# RECEIVER.net
KiCad netlist of a schematic drawn in EAGLE
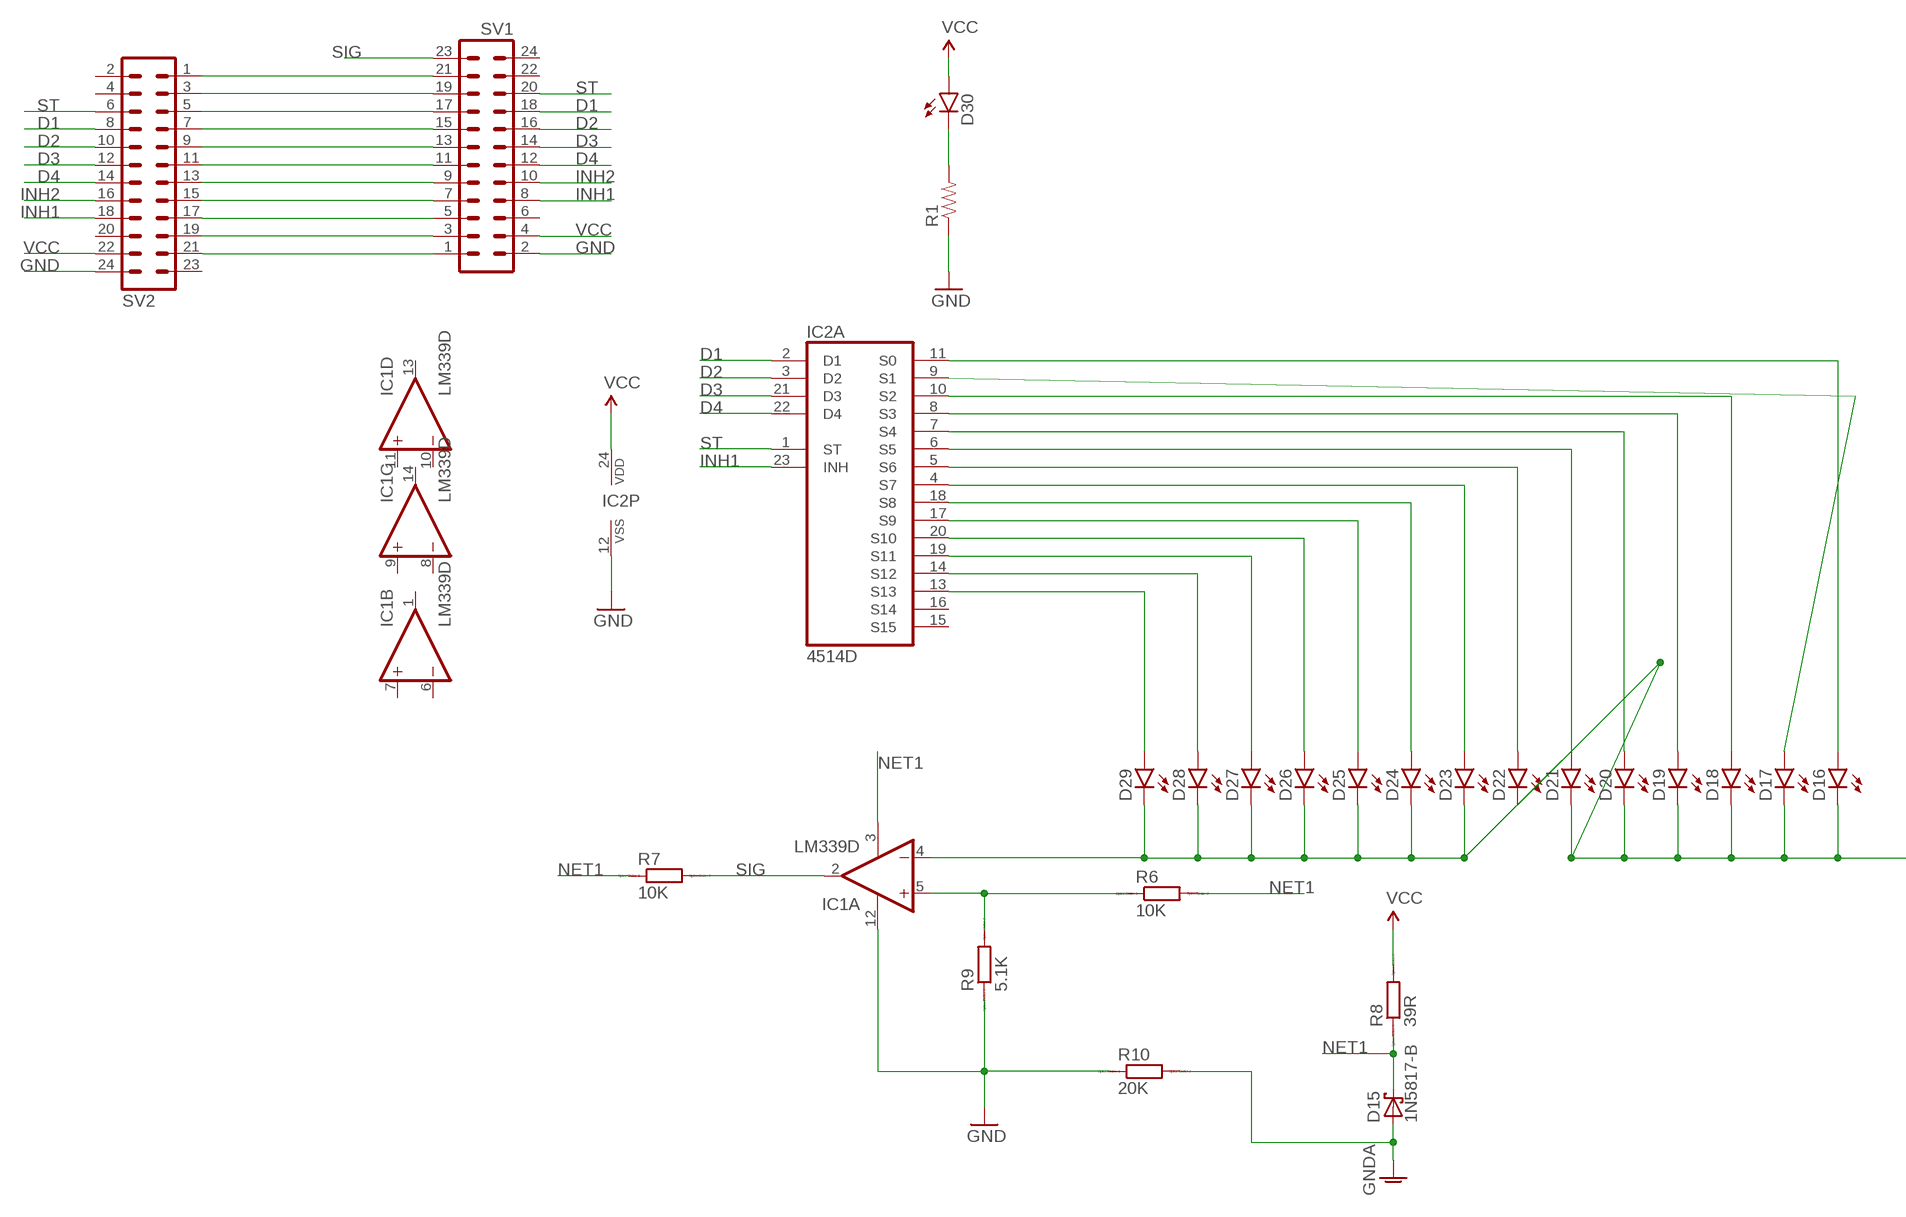
[diagram p0: schematic, sheet 1, part 1 of 2]
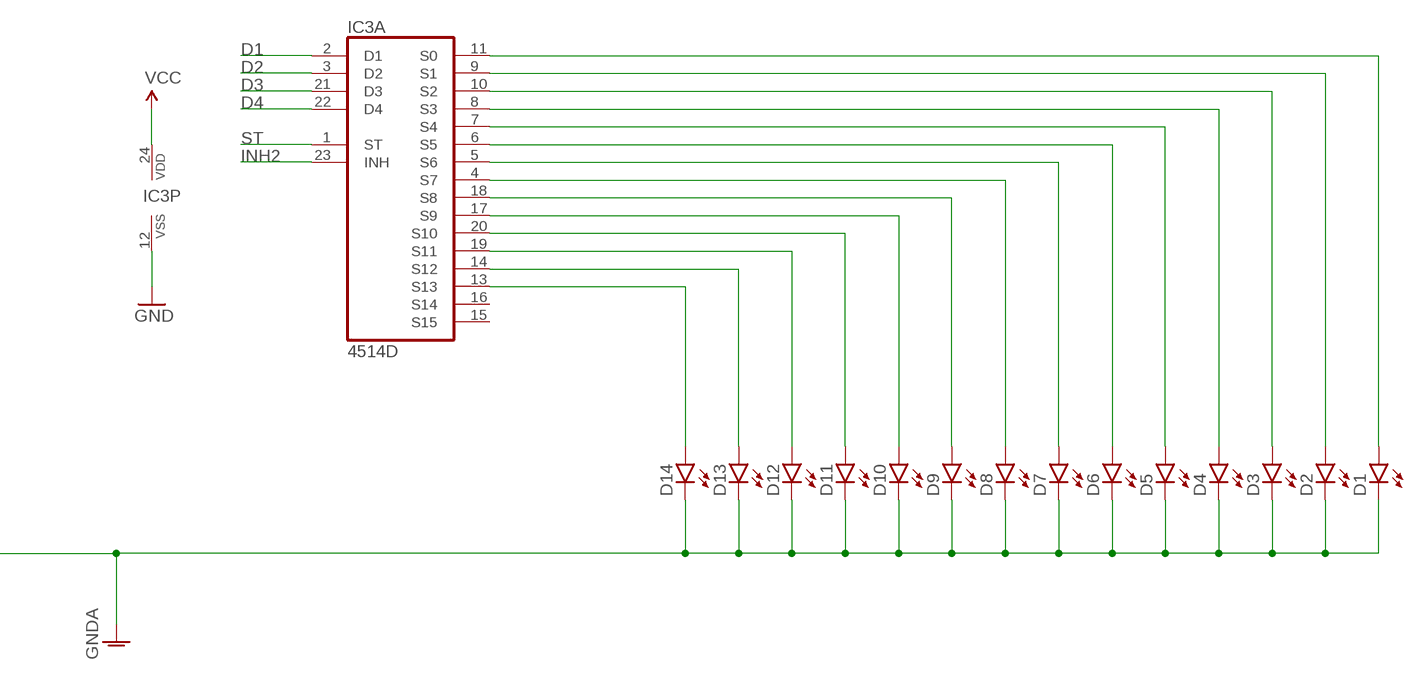
[diagram p1: schematic, sheet 1, part 2 of 2]

(export (version "E")
  (design (tool "Eeschema 10.0.6"))
  (components
    (comp (ref "D1")
      (value "LED5MM")
      (footprint "eagle-import:LED5MM")
      (libsource (lib "eagle-import") (part "LED5MM"))
    )
    (comp (ref "D2")
      (value "LED5MM")
      (footprint "eagle-import:LED5MM")
      (libsource (lib "eagle-import") (part "LED5MM"))
    )
    (comp (ref "D3")
      (value "LED5MM")
      (footprint "eagle-import:LED5MM")
      (libsource (lib "eagle-import") (part "LED5MM"))
    )
    (comp (ref "D4")
      (value "LED5MM")
      (footprint "eagle-import:LED5MM")
      (libsource (lib "eagle-import") (part "LED5MM"))
    )
    (comp (ref "D5")
      (value "LED5MM")
      (footprint "eagle-import:LED5MM")
      (libsource (lib "eagle-import") (part "LED5MM"))
    )
    (comp (ref "D6")
      (value "LED5MM")
      (footprint "eagle-import:LED5MM")
      (libsource (lib "eagle-import") (part "LED5MM"))
    )
    (comp (ref "D7")
      (value "LED5MM")
      (footprint "eagle-import:LED5MM")
      (libsource (lib "eagle-import") (part "LED5MM"))
    )
    (comp (ref "D8")
      (value "LED5MM")
      (footprint "eagle-import:LED5MM")
      (libsource (lib "eagle-import") (part "LED5MM"))
    )
    (comp (ref "D9")
      (value "LED5MM")
      (footprint "eagle-import:LED5MM")
      (libsource (lib "eagle-import") (part "LED5MM"))
    )
    (comp (ref "D10")
      (value "LED5MM")
      (footprint "eagle-import:LED5MM")
      (libsource (lib "eagle-import") (part "LED5MM"))
    )
    (comp (ref "D11")
      (value "LED5MM")
      (footprint "eagle-import:LED5MM")
      (libsource (lib "eagle-import") (part "LED5MM"))
    )
    (comp (ref "D12")
      (value "LED5MM")
      (footprint "eagle-import:LED5MM")
      (libsource (lib "eagle-import") (part "LED5MM"))
    )
    (comp (ref "D13")
      (value "LED5MM")
      (footprint "eagle-import:LED5MM")
      (libsource (lib "eagle-import") (part "LED5MM"))
    )
    (comp (ref "D14")
      (value "LED5MM")
      (footprint "eagle-import:LED5MM")
      (libsource (lib "eagle-import") (part "LED5MM"))
    )
    (comp (ref "D15")
      (value "1N5817-B")
      (footprint "eagle-import:DO41-7.6")
      (libsource (lib "eagle-import") (part "1N5817-B"))
    )
    (comp (ref "D16")
      (value "LED5MM")
      (footprint "eagle-import:LED5MM")
      (libsource (lib "eagle-import") (part "LED5MM"))
    )
    (comp (ref "D17")
      (value "LED5MM")
      (footprint "eagle-import:LED5MM")
      (libsource (lib "eagle-import") (part "LED5MM"))
    )
    (comp (ref "D18")
      (value "LED5MM")
      (footprint "eagle-import:LED5MM")
      (libsource (lib "eagle-import") (part "LED5MM"))
    )
    (comp (ref "D19")
      (value "LED5MM")
      (footprint "eagle-import:LED5MM")
      (libsource (lib "eagle-import") (part "LED5MM"))
    )
    (comp (ref "D20")
      (value "LED5MM")
      (footprint "eagle-import:LED5MM")
      (libsource (lib "eagle-import") (part "LED5MM"))
    )
    (comp (ref "D21")
      (value "LED5MM")
      (footprint "eagle-import:LED5MM")
      (libsource (lib "eagle-import") (part "LED5MM"))
    )
    (comp (ref "D22")
      (value "LED5MM")
      (footprint "eagle-import:LED5MM")
      (libsource (lib "eagle-import") (part "LED5MM"))
    )
    (comp (ref "D23")
      (value "LED5MM")
      (footprint "eagle-import:LED5MM")
      (libsource (lib "eagle-import") (part "LED5MM"))
    )
    (comp (ref "D24")
      (value "LED5MM")
      (footprint "eagle-import:LED5MM")
      (libsource (lib "eagle-import") (part "LED5MM"))
    )
    (comp (ref "D25")
      (value "LED5MM")
      (footprint "eagle-import:LED5MM")
      (libsource (lib "eagle-import") (part "LED5MM"))
    )
    (comp (ref "D26")
      (value "LED5MM")
      (footprint "eagle-import:LED5MM")
      (libsource (lib "eagle-import") (part "LED5MM"))
    )
    (comp (ref "D27")
      (value "LED5MM")
      (footprint "eagle-import:LED5MM")
      (libsource (lib "eagle-import") (part "LED5MM"))
    )
    (comp (ref "D28")
      (value "LED5MM")
      (footprint "eagle-import:LED5MM")
      (libsource (lib "eagle-import") (part "LED5MM"))
    )
    (comp (ref "D29")
      (value "LED5MM")
      (footprint "eagle-import:LED5MM")
      (libsource (lib "eagle-import") (part "LED5MM"))
    )
    (comp (ref "D30")
      (value "LED1206")
      (footprint "eagle-import:LED-1206")
      (libsource (lib "eagle-import") (part "LED1206"))
    )
    (comp (ref "IC1")
      (value "LM339D")
      (footprint "eagle-import:SO14")
      (libsource (lib "eagle-import") (part "LM339D"))
    )
    (comp (ref "IC2")
      (value "4514D")
      (footprint "eagle-import:SO24W")
      (libsource (lib "eagle-import") (part "4514D"))
    )
    (comp (ref "IC3")
      (value "4514D")
      (footprint "eagle-import:SO24W")
      (libsource (lib "eagle-import") (part "4514D"))
    )
    (comp (ref "R1")
      (value "RESISTOR1206")
      (footprint "eagle-import:1206")
      (libsource (lib "eagle-import") (part "RESISTOR1206"))
    )
    (comp (ref "R6")
      (value "10K")
      (footprint "eagle-import:0207_10")
      (libsource (lib "eagle-import") (part "R0207/10"))
    )
    (comp (ref "R7")
      (value "10K")
      (footprint "eagle-import:0207_10")
      (libsource (lib "eagle-import") (part "R0207/10"))
    )
    (comp (ref "R8")
      (value "39R")
      (footprint "eagle-import:0207_10")
      (libsource (lib "eagle-import") (part "R0207/10"))
    )
    (comp (ref "R9")
      (value "5.1K")
      (footprint "eagle-import:0207_10")
      (libsource (lib "eagle-import") (part "R0207/10"))
    )
    (comp (ref "R10")
      (value "20K")
      (footprint "eagle-import:0207_10")
      (libsource (lib "eagle-import") (part "R0207/10"))
    )
    (comp (ref "SV1")
      (value "MA12-2W")
      (footprint "eagle-import:MA12-2W")
      (libsource (lib "eagle-import") (part "MA12-2W"))
    )
    (comp (ref "SV2")
      (value "MA12-2W")
      (footprint "eagle-import:MA12-2W")
      (libsource (lib "eagle-import") (part "MA12-2W"))
    )
  )
  (nets
    (net (code "1") (name "/D1") (class "Default")
      (node (ref "IC2") (pin "2") (pinfunction "D1_2") (pintype "input"))
      (node (ref "IC3") (pin "2") (pinfunction "D1_2") (pintype "input"))
      (node (ref "SV1") (pin "18") (pinfunction "18_18") (pintype "passive"))
      (node (ref "SV2") (pin "8") (pinfunction "8_8") (pintype "passive"))
    )
    (net (code "2") (name "/D2") (class "Default")
      (node (ref "IC2") (pin "3") (pinfunction "D2_3") (pintype "input"))
      (node (ref "IC3") (pin "3") (pinfunction "D2_3") (pintype "input"))
      (node (ref "SV1") (pin "16") (pinfunction "16_16") (pintype "passive"))
      (node (ref "SV2") (pin "10") (pinfunction "10_10") (pintype "passive"))
    )
    (net (code "3") (name "/D3") (class "Default")
      (node (ref "IC2") (pin "21") (pinfunction "D3_21") (pintype "input"))
      (node (ref "IC3") (pin "21") (pinfunction "D3_21") (pintype "input"))
      (node (ref "SV1") (pin "14") (pinfunction "14_14") (pintype "passive"))
      (node (ref "SV2") (pin "12") (pinfunction "12_12") (pintype "passive"))
    )
    (net (code "4") (name "/D4") (class "Default")
      (node (ref "IC2") (pin "22") (pinfunction "D4_22") (pintype "input"))
      (node (ref "IC3") (pin "22") (pinfunction "D4_22") (pintype "input"))
      (node (ref "SV1") (pin "12") (pinfunction "12_12") (pintype "passive"))
      (node (ref "SV2") (pin "14") (pinfunction "14_14") (pintype "passive"))
    )
    (net (code "5") (name "/INH1") (class "Default")
      (node (ref "IC2") (pin "23") (pinfunction "INH_23") (pintype "input"))
      (node (ref "SV1") (pin "8") (pinfunction "8_8") (pintype "passive"))
      (node (ref "SV2") (pin "18") (pinfunction "18_18") (pintype "passive"))
    )
    (net (code "6") (name "/INH2") (class "Default")
      (node (ref "IC3") (pin "23") (pinfunction "INH_23") (pintype "input"))
      (node (ref "SV1") (pin "10") (pinfunction "10_10") (pintype "passive"))
      (node (ref "SV2") (pin "16") (pinfunction "16_16") (pintype "passive"))
    )
    (net (code "7") (name "/NET1") (class "Default")
      (node (ref "D15") (pin "C") (pinfunction "C_C") (pintype "passive"))
      (node (ref "IC1") (pin "3") (pinfunction "V+_3") (pintype "power_in"))
      (node (ref "R6") (pin "2") (pinfunction "2_2") (pintype "passive"))
      (node (ref "R7") (pin "1") (pinfunction "1_1") (pintype "passive"))
      (node (ref "R8") (pin "1") (pinfunction "1_1") (pintype "passive"))
    )
    (net (code "8") (name "/SIG") (class "Default")
      (node (ref "IC1") (pin "2") (pinfunction "OUT_2") (pintype "open_collector"))
      (node (ref "R7") (pin "2") (pinfunction "2_2") (pintype "passive"))
      (node (ref "SV1") (pin "23") (pinfunction "23_23") (pintype "passive"))
    )
    (net (code "9") (name "/ST") (class "Default")
      (node (ref "IC2") (pin "1") (pinfunction "ST_1") (pintype "input"))
      (node (ref "IC3") (pin "1") (pinfunction "ST_1") (pintype "input"))
      (node (ref "SV1") (pin "20") (pinfunction "20_20") (pintype "passive"))
      (node (ref "SV2") (pin "6") (pinfunction "6_6") (pintype "passive"))
    )
    (net (code "10") (name "GND") (class "Default")
      (node (ref "IC1") (pin "12") (pinfunction "GND_12") (pintype "power_in"))
      (node (ref "IC2") (pin "12") (pinfunction "VSS_12") (pintype "power_in"))
      (node (ref "IC3") (pin "12") (pinfunction "VSS_12") (pintype "power_in"))
      (node (ref "R1") (pin "1") (pinfunction "1_1") (pintype "passive"))
      (node (ref "R10") (pin "1") (pinfunction "1_1") (pintype "passive"))
      (node (ref "R9") (pin "1") (pinfunction "1_1") (pintype "passive"))
      (node (ref "SV1") (pin "2") (pinfunction "2_2") (pintype "passive"))
      (node (ref "SV2") (pin "24") (pinfunction "24_24") (pintype "passive"))
    )
    (net (code "11") (name "GNDA") (class "Default")
      (node (ref "D1") (pin "K") (pinfunction "C_K") (pintype "passive"))
      (node (ref "D10") (pin "K") (pinfunction "C_K") (pintype "passive"))
      (node (ref "D11") (pin "K") (pinfunction "C_K") (pintype "passive"))
      (node (ref "D12") (pin "K") (pinfunction "C_K") (pintype "passive"))
      (node (ref "D13") (pin "K") (pinfunction "C_K") (pintype "passive"))
      (node (ref "D14") (pin "K") (pinfunction "C_K") (pintype "passive"))
      (node (ref "D15") (pin "A") (pinfunction "A_A") (pintype "passive"))
      (node (ref "D16") (pin "K") (pinfunction "C_K") (pintype "passive"))
      (node (ref "D17") (pin "K") (pinfunction "C_K") (pintype "passive"))
      (node (ref "D18") (pin "K") (pinfunction "C_K") (pintype "passive"))
      (node (ref "D19") (pin "K") (pinfunction "C_K") (pintype "passive"))
      (node (ref "D2") (pin "K") (pinfunction "C_K") (pintype "passive"))
      (node (ref "D20") (pin "K") (pinfunction "C_K") (pintype "passive"))
      (node (ref "D21") (pin "K") (pinfunction "C_K") (pintype "passive"))
      (node (ref "D22") (pin "K") (pinfunction "C_K") (pintype "passive"))
      (node (ref "D23") (pin "K") (pinfunction "C_K") (pintype "passive"))
      (node (ref "D24") (pin "K") (pinfunction "C_K") (pintype "passive"))
      (node (ref "D25") (pin "K") (pinfunction "C_K") (pintype "passive"))
      (node (ref "D26") (pin "K") (pinfunction "C_K") (pintype "passive"))
      (node (ref "D27") (pin "K") (pinfunction "C_K") (pintype "passive"))
      (node (ref "D28") (pin "K") (pinfunction "C_K") (pintype "passive"))
      (node (ref "D29") (pin "K") (pinfunction "C_K") (pintype "passive"))
      (node (ref "D3") (pin "K") (pinfunction "C_K") (pintype "passive"))
      (node (ref "D4") (pin "K") (pinfunction "C_K") (pintype "passive"))
      (node (ref "D5") (pin "K") (pinfunction "C_K") (pintype "passive"))
      (node (ref "D6") (pin "K") (pinfunction "C_K") (pintype "passive"))
      (node (ref "D7") (pin "K") (pinfunction "C_K") (pintype "passive"))
      (node (ref "D8") (pin "K") (pinfunction "C_K") (pintype "passive"))
      (node (ref "D9") (pin "K") (pinfunction "C_K") (pintype "passive"))
      (node (ref "IC1") (pin "4") (pinfunction "-IN_4") (pintype "input"))
      (node (ref "R10") (pin "2") (pinfunction "2_2") (pintype "passive"))
    )
    (net (code "12") (name "Net-(D30-PadC)") (class "Default")
      (node (ref "D30") (pin "C") (pinfunction "C_C") (pintype "passive"))
      (node (ref "R1") (pin "2") (pinfunction "2_2") (pintype "passive"))
    )
    (net (code "13") (name "Net-(IC1A-+IN)") (class "Default")
      (node (ref "IC1") (pin "5") (pinfunction "+IN_5") (pintype "input"))
      (node (ref "R6") (pin "1") (pinfunction "1_1") (pintype "passive"))
      (node (ref "R9") (pin "2") (pinfunction "2_2") (pintype "passive"))
    )
    (net (code "14") (name "Net-(IC2A-S0)") (class "Default")
      (node (ref "D16") (pin "A") (pinfunction "A_A") (pintype "passive"))
      (node (ref "IC2") (pin "11") (pinfunction "S0_11") (pintype "output"))
    )
    (net (code "15") (name "Net-(IC2A-S1)") (class "Default")
      (node (ref "D17") (pin "A") (pinfunction "A_A") (pintype "passive"))
      (node (ref "IC2") (pin "9") (pinfunction "S1_9") (pintype "output"))
    )
    (net (code "16") (name "Net-(IC2A-S2)") (class "Default")
      (node (ref "D18") (pin "A") (pinfunction "A_A") (pintype "passive"))
      (node (ref "IC2") (pin "10") (pinfunction "S2_10") (pintype "output"))
    )
    (net (code "17") (name "Net-(IC2A-S3)") (class "Default")
      (node (ref "D19") (pin "A") (pinfunction "A_A") (pintype "passive"))
      (node (ref "IC2") (pin "8") (pinfunction "S3_8") (pintype "output"))
    )
    (net (code "18") (name "Net-(IC2A-S4)") (class "Default")
      (node (ref "D20") (pin "A") (pinfunction "A_A") (pintype "passive"))
      (node (ref "IC2") (pin "7") (pinfunction "S4_7") (pintype "output"))
    )
    (net (code "19") (name "Net-(IC2A-S5)") (class "Default")
      (node (ref "D21") (pin "A") (pinfunction "A_A") (pintype "passive"))
      (node (ref "IC2") (pin "6") (pinfunction "S5_6") (pintype "output"))
    )
    (net (code "20") (name "Net-(IC2A-S6)") (class "Default")
      (node (ref "D22") (pin "A") (pinfunction "A_A") (pintype "passive"))
      (node (ref "IC2") (pin "5") (pinfunction "S6_5") (pintype "output"))
    )
    (net (code "21") (name "Net-(IC2A-S7)") (class "Default")
      (node (ref "D23") (pin "A") (pinfunction "A_A") (pintype "passive"))
      (node (ref "IC2") (pin "4") (pinfunction "S7_4") (pintype "output"))
    )
    (net (code "22") (name "Net-(IC2A-S8)") (class "Default")
      (node (ref "D24") (pin "A") (pinfunction "A_A") (pintype "passive"))
      (node (ref "IC2") (pin "18") (pinfunction "S8_18") (pintype "output"))
    )
    (net (code "23") (name "Net-(IC2A-S9)") (class "Default")
      (node (ref "D25") (pin "A") (pinfunction "A_A") (pintype "passive"))
      (node (ref "IC2") (pin "17") (pinfunction "S9_17") (pintype "output"))
    )
    (net (code "24") (name "Net-(IC2A-S10)") (class "Default")
      (node (ref "D26") (pin "A") (pinfunction "A_A") (pintype "passive"))
      (node (ref "IC2") (pin "20") (pinfunction "S10_20") (pintype "output"))
    )
    (net (code "25") (name "Net-(IC2A-S11)") (class "Default")
      (node (ref "D27") (pin "A") (pinfunction "A_A") (pintype "passive"))
      (node (ref "IC2") (pin "19") (pinfunction "S11_19") (pintype "output"))
    )
    (net (code "26") (name "Net-(IC2A-S12)") (class "Default")
      (node (ref "D28") (pin "A") (pinfunction "A_A") (pintype "passive"))
      (node (ref "IC2") (pin "14") (pinfunction "S12_14") (pintype "output"))
    )
    (net (code "27") (name "Net-(IC2A-S13)") (class "Default")
      (node (ref "D29") (pin "A") (pinfunction "A_A") (pintype "passive"))
      (node (ref "IC2") (pin "13") (pinfunction "S13_13") (pintype "output"))
    )
    (net (code "28") (name "Net-(IC3A-S0)") (class "Default")
      (node (ref "D1") (pin "A") (pinfunction "A_A") (pintype "passive"))
      (node (ref "IC3") (pin "11") (pinfunction "S0_11") (pintype "output"))
    )
    (net (code "29") (name "Net-(IC3A-S1)") (class "Default")
      (node (ref "D2") (pin "A") (pinfunction "A_A") (pintype "passive"))
      (node (ref "IC3") (pin "9") (pinfunction "S1_9") (pintype "output"))
    )
    (net (code "30") (name "Net-(IC3A-S2)") (class "Default")
      (node (ref "D3") (pin "A") (pinfunction "A_A") (pintype "passive"))
      (node (ref "IC3") (pin "10") (pinfunction "S2_10") (pintype "output"))
    )
    (net (code "31") (name "Net-(IC3A-S3)") (class "Default")
      (node (ref "D4") (pin "A") (pinfunction "A_A") (pintype "passive"))
      (node (ref "IC3") (pin "8") (pinfunction "S3_8") (pintype "output"))
    )
    (net (code "32") (name "Net-(IC3A-S4)") (class "Default")
      (node (ref "D5") (pin "A") (pinfunction "A_A") (pintype "passive"))
      (node (ref "IC3") (pin "7") (pinfunction "S4_7") (pintype "output"))
    )
    (net (code "33") (name "Net-(IC3A-S5)") (class "Default")
      (node (ref "D6") (pin "A") (pinfunction "A_A") (pintype "passive"))
      (node (ref "IC3") (pin "6") (pinfunction "S5_6") (pintype "output"))
    )
    (net (code "34") (name "Net-(IC3A-S6)") (class "Default")
      (node (ref "D7") (pin "A") (pinfunction "A_A") (pintype "passive"))
      (node (ref "IC3") (pin "5") (pinfunction "S6_5") (pintype "output"))
    )
    (net (code "35") (name "Net-(IC3A-S7)") (class "Default")
      (node (ref "D8") (pin "A") (pinfunction "A_A") (pintype "passive"))
      (node (ref "IC3") (pin "4") (pinfunction "S7_4") (pintype "output"))
    )
    (net (code "36") (name "Net-(IC3A-S8)") (class "Default")
      (node (ref "D9") (pin "A") (pinfunction "A_A") (pintype "passive"))
      (node (ref "IC3") (pin "18") (pinfunction "S8_18") (pintype "output"))
    )
    (net (code "37") (name "Net-(IC3A-S9)") (class "Default")
      (node (ref "D10") (pin "A") (pinfunction "A_A") (pintype "passive"))
      (node (ref "IC3") (pin "17") (pinfunction "S9_17") (pintype "output"))
    )
    (net (code "38") (name "Net-(IC3A-S10)") (class "Default")
      (node (ref "D11") (pin "A") (pinfunction "A_A") (pintype "passive"))
      (node (ref "IC3") (pin "20") (pinfunction "S10_20") (pintype "output"))
    )
    (net (code "39") (name "Net-(IC3A-S11)") (class "Default")
      (node (ref "D12") (pin "A") (pinfunction "A_A") (pintype "passive"))
      (node (ref "IC3") (pin "19") (pinfunction "S11_19") (pintype "output"))
    )
    (net (code "40") (name "Net-(IC3A-S12)") (class "Default")
      (node (ref "D13") (pin "A") (pinfunction "A_A") (pintype "passive"))
      (node (ref "IC3") (pin "14") (pinfunction "S12_14") (pintype "output"))
    )
    (net (code "41") (name "Net-(IC3A-S13)") (class "Default")
      (node (ref "D14") (pin "A") (pinfunction "A_A") (pintype "passive"))
      (node (ref "IC3") (pin "13") (pinfunction "S13_13") (pintype "output"))
    )
    (net (code "42") (name "Net-(SV1-Pad1)") (class "Default")
      (node (ref "SV1") (pin "1") (pinfunction "1_1") (pintype "passive"))
      (node (ref "SV2") (pin "21") (pinfunction "21_21") (pintype "passive"))
    )
    (net (code "43") (name "Net-(SV1-Pad3)") (class "Default")
      (node (ref "SV1") (pin "3") (pinfunction "3_3") (pintype "passive"))
      (node (ref "SV2") (pin "19") (pinfunction "19_19") (pintype "passive"))
    )
    (net (code "44") (name "Net-(SV1-Pad5)") (class "Default")
      (node (ref "SV1") (pin "5") (pinfunction "5_5") (pintype "passive"))
      (node (ref "SV2") (pin "17") (pinfunction "17_17") (pintype "passive"))
    )
    (net (code "45") (name "Net-(SV1-Pad7)") (class "Default")
      (node (ref "SV1") (pin "7") (pinfunction "7_7") (pintype "passive"))
      (node (ref "SV2") (pin "15") (pinfunction "15_15") (pintype "passive"))
    )
    (net (code "46") (name "Net-(SV1-Pad9)") (class "Default")
      (node (ref "SV1") (pin "9") (pinfunction "9_9") (pintype "passive"))
      (node (ref "SV2") (pin "13") (pinfunction "13_13") (pintype "passive"))
    )
    (net (code "47") (name "Net-(SV1-Pad11)") (class "Default")
      (node (ref "SV1") (pin "11") (pinfunction "11_11") (pintype "passive"))
      (node (ref "SV2") (pin "11") (pinfunction "11_11") (pintype "passive"))
    )
    (net (code "48") (name "Net-(SV1-Pad13)") (class "Default")
      (node (ref "SV1") (pin "13") (pinfunction "13_13") (pintype "passive"))
      (node (ref "SV2") (pin "9") (pinfunction "9_9") (pintype "passive"))
    )
    (net (code "49") (name "Net-(SV1-Pad15)") (class "Default")
      (node (ref "SV1") (pin "15") (pinfunction "15_15") (pintype "passive"))
      (node (ref "SV2") (pin "7") (pinfunction "7_7") (pintype "passive"))
    )
    (net (code "50") (name "Net-(SV1-Pad17)") (class "Default")
      (node (ref "SV1") (pin "17") (pinfunction "17_17") (pintype "passive"))
      (node (ref "SV2") (pin "5") (pinfunction "5_5") (pintype "passive"))
    )
    (net (code "51") (name "Net-(SV1-Pad19)") (class "Default")
      (node (ref "SV1") (pin "19") (pinfunction "19_19") (pintype "passive"))
      (node (ref "SV2") (pin "3") (pinfunction "3_3") (pintype "passive"))
    )
    (net (code "52") (name "Net-(SV1-Pad21)") (class "Default")
      (node (ref "SV1") (pin "21") (pinfunction "21_21") (pintype "passive"))
      (node (ref "SV2") (pin "1") (pinfunction "1_1") (pintype "passive"))
    )
    (net (code "53") (name "VCC") (class "Default")
      (node (ref "D30") (pin "A") (pinfunction "A_A") (pintype "passive"))
      (node (ref "IC2") (pin "24") (pinfunction "VDD_24") (pintype "power_in"))
      (node (ref "IC3") (pin "24") (pinfunction "VDD_24") (pintype "power_in"))
      (node (ref "R8") (pin "2") (pinfunction "2_2") (pintype "passive"))
      (node (ref "SV1") (pin "4") (pinfunction "4_4") (pintype "passive"))
      (node (ref "SV2") (pin "22") (pinfunction "22_22") (pintype "passive"))
    )
    (net (code "54") (name "unconnected-(IC1B-+IN-Pad7)") (class "Default")
      (node (ref "IC1") (pin "7") (pinfunction "+IN_7") (pintype "input"))
    )
    (net (code "55") (name "unconnected-(IC1B--IN-Pad6)") (class "Default")
      (node (ref "IC1") (pin "6") (pinfunction "-IN_6") (pintype "input"))
    )
    (net (code "56") (name "unconnected-(IC1B-OUT-Pad1)") (class "Default")
      (node (ref "IC1") (pin "1") (pinfunction "OUT_1") (pintype "open_collector"))
    )
    (net (code "57") (name "unconnected-(IC1C-+IN-Pad9)") (class "Default")
      (node (ref "IC1") (pin "9") (pinfunction "+IN_9") (pintype "input"))
    )
    (net (code "58") (name "unconnected-(IC1C--IN-Pad8)") (class "Default")
      (node (ref "IC1") (pin "8") (pinfunction "-IN_8") (pintype "input"))
    )
    (net (code "59") (name "unconnected-(IC1C-OUT-Pad14)") (class "Default")
      (node (ref "IC1") (pin "14") (pinfunction "OUT_14") (pintype "open_collector"))
    )
    (net (code "60") (name "unconnected-(IC1D-+IN-Pad11)") (class "Default")
      (node (ref "IC1") (pin "11") (pinfunction "+IN_11") (pintype "input"))
    )
    (net (code "61") (name "unconnected-(IC1D--IN-Pad10)") (class "Default")
      (node (ref "IC1") (pin "10") (pinfunction "-IN_10") (pintype "input"))
    )
    (net (code "62") (name "unconnected-(IC1D-OUT-Pad13)") (class "Default")
      (node (ref "IC1") (pin "13") (pinfunction "OUT_13") (pintype "open_collector"))
    )
    (net (code "63") (name "unconnected-(IC2A-S14-Pad16)") (class "Default")
      (node (ref "IC2") (pin "16") (pinfunction "S14_16") (pintype "output"))
    )
    (net (code "64") (name "unconnected-(IC2A-S15-Pad15)") (class "Default")
      (node (ref "IC2") (pin "15") (pinfunction "S15_15") (pintype "output"))
    )
    (net (code "65") (name "unconnected-(IC3A-S14-Pad16)") (class "Default")
      (node (ref "IC3") (pin "16") (pinfunction "S14_16") (pintype "output"))
    )
    (net (code "66") (name "unconnected-(IC3A-S15-Pad15)") (class "Default")
      (node (ref "IC3") (pin "15") (pinfunction "S15_15") (pintype "output"))
    )
    (net (code "67") (name "unconnected-(SV1-Pad6)") (class "Default")
      (node (ref "SV1") (pin "6") (pinfunction "6_6") (pintype "passive"))
    )
    (net (code "68") (name "unconnected-(SV1-Pad22)") (class "Default")
      (node (ref "SV1") (pin "22") (pinfunction "22_22") (pintype "passive"))
    )
    (net (code "69") (name "unconnected-(SV1-Pad24)") (class "Default")
      (node (ref "SV1") (pin "24") (pinfunction "24_24") (pintype "passive"))
    )
    (net (code "70") (name "unconnected-(SV2-Pad2)") (class "Default")
      (node (ref "SV2") (pin "2") (pinfunction "2_2") (pintype "passive"))
    )
    (net (code "71") (name "unconnected-(SV2-Pad4)") (class "Default")
      (node (ref "SV2") (pin "4") (pinfunction "4_4") (pintype "passive"))
    )
    (net (code "72") (name "unconnected-(SV2-Pad20)") (class "Default")
      (node (ref "SV2") (pin "20") (pinfunction "20_20") (pintype "passive"))
    )
    (net (code "73") (name "unconnected-(SV2-Pad23)") (class "Default")
      (node (ref "SV2") (pin "23") (pinfunction "23_23") (pintype "passive"))
    )
  )
)
